# anemo4.net
KiCad netlist of a schematic drawn in EAGLE
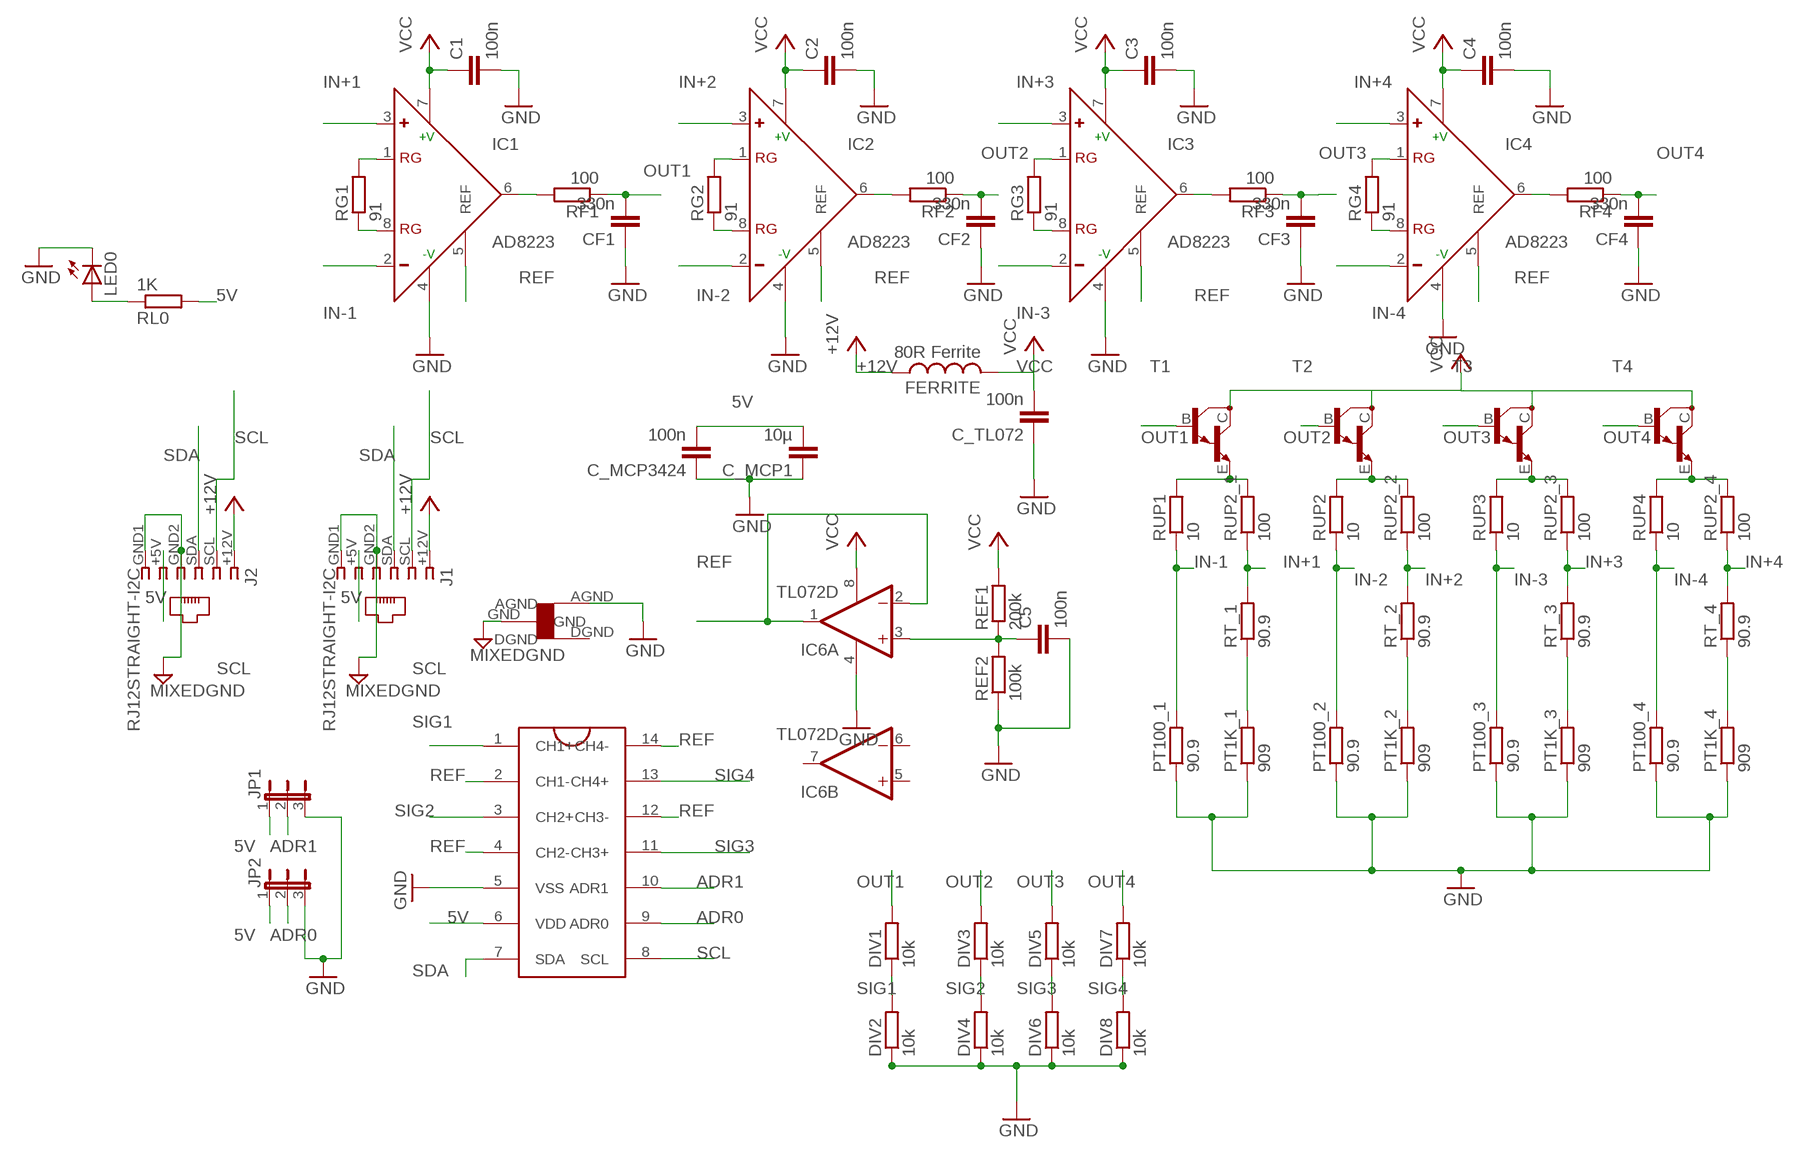
[diagram p0: schematic, sheet 1]

(export (version "E")
  (design (tool "Eeschema 10.0.6"))
  (components
    (comp (ref "C1")
      (value "100n")
      (footprint "eagle-import:C1206")
      (libsource (lib "eagle-import") (part "C-EUC1206"))
    )
    (comp (ref "C2")
      (value "100n")
      (footprint "eagle-import:C1206")
      (libsource (lib "eagle-import") (part "C-EUC1206"))
    )
    (comp (ref "C3")
      (value "100n")
      (footprint "eagle-import:C1206")
      (libsource (lib "eagle-import") (part "C-EUC1206"))
    )
    (comp (ref "C4")
      (value "100n")
      (footprint "eagle-import:C1206")
      (libsource (lib "eagle-import") (part "C-EUC1206"))
    )
    (comp (ref "C5")
      (value "100n")
      (footprint "eagle-import:C1206")
      (libsource (lib "eagle-import") (part "C-EUC1206"))
    )
    (comp (ref "CF1")
      (value "330n")
      (footprint "eagle-import:C1206")
      (libsource (lib "eagle-import") (part "C-EUC1206"))
    )
    (comp (ref "CF2")
      (value "330n")
      (footprint "eagle-import:C1206")
      (libsource (lib "eagle-import") (part "C-EUC1206"))
    )
    (comp (ref "CF3")
      (value "330n")
      (footprint "eagle-import:C1206")
      (libsource (lib "eagle-import") (part "C-EUC1206"))
    )
    (comp (ref "CF4")
      (value "330n")
      (footprint "eagle-import:C1206")
      (libsource (lib "eagle-import") (part "C-EUC1206"))
    )
    (comp (ref "C_MCP1")
      (value "10µ")
      (footprint "eagle-import:C1206")
      (libsource (lib "eagle-import") (part "C-EUC1206"))
    )
    (comp (ref "C_MCP3424")
      (value "100n")
      (footprint "eagle-import:C1206")
      (libsource (lib "eagle-import") (part "C-EUC1206"))
    )
    (comp (ref "C_TL072")
      (value "100n")
      (footprint "eagle-import:C1206")
      (libsource (lib "eagle-import") (part "C-EUC1206"))
    )
    (comp (ref "DIV1")
      (value "10k")
      (footprint "eagle-import:M1206")
      (libsource (lib "eagle-import") (part "R-EU_M1206"))
    )
    (comp (ref "DIV2")
      (value "10k")
      (footprint "eagle-import:M1206")
      (libsource (lib "eagle-import") (part "R-EU_M1206"))
    )
    (comp (ref "DIV3")
      (value "10k")
      (footprint "eagle-import:M1206")
      (libsource (lib "eagle-import") (part "R-EU_M1206"))
    )
    (comp (ref "DIV4")
      (value "10k")
      (footprint "eagle-import:M1206")
      (libsource (lib "eagle-import") (part "R-EU_M1206"))
    )
    (comp (ref "DIV5")
      (value "10k")
      (footprint "eagle-import:M1206")
      (libsource (lib "eagle-import") (part "R-EU_M1206"))
    )
    (comp (ref "DIV6")
      (value "10k")
      (footprint "eagle-import:M1206")
      (libsource (lib "eagle-import") (part "R-EU_M1206"))
    )
    (comp (ref "DIV7")
      (value "10k")
      (footprint "eagle-import:M1206")
      (libsource (lib "eagle-import") (part "R-EU_M1206"))
    )
    (comp (ref "DIV8")
      (value "10k")
      (footprint "eagle-import:M1206")
      (libsource (lib "eagle-import") (part "R-EU_M1206"))
    )
    (comp (ref "FERRITE")
      (value "80R Ferrite")
      (footprint "eagle-import:L3216C")
      (libsource (lib "eagle-import") (part "L-USL3216C"))
    )
    (comp (ref "IC1")
      (value "AD8223")
      (footprint "eagle-import:SO8")
      (fields (field (name "MPN") "AD620AR"))
      (libsource (lib "eagle-import") (part "AD620R"))
    )
    (comp (ref "IC2")
      (value "AD8223")
      (footprint "eagle-import:SO8")
      (fields (field (name "MPN") "AD620AR"))
      (libsource (lib "eagle-import") (part "AD620R"))
    )
    (comp (ref "IC3")
      (value "AD8223")
      (footprint "eagle-import:SO8")
      (fields (field (name "MPN") "AD620AR"))
      (libsource (lib "eagle-import") (part "AD620R"))
    )
    (comp (ref "IC4")
      (value "AD8223")
      (footprint "eagle-import:SO8")
      (fields (field (name "MPN") "AD620AR"))
      (libsource (lib "eagle-import") (part "AD620R"))
    )
    (comp (ref "IC6")
      (value "TL072D")
      (footprint "eagle-import:SO08")
      (libsource (lib "eagle-import") (part "TL072D"))
    )
    (comp (ref "J1")
      (value "RJ12STRAIGHT-I2C")
      (footprint "eagle-import:RJ12-STRAIGHT-I2C")
      (libsource (lib "eagle-import") (part "RJ12STRAIGHT-I2C"))
    )
    (comp (ref "J2")
      (value "RJ12STRAIGHT-I2C")
      (footprint "eagle-import:RJ12-STRAIGHT-I2C")
      (libsource (lib "eagle-import") (part "RJ12STRAIGHT-I2C"))
    )
    (comp (ref "JP1")
      (value "JP2E")
      (footprint "eagle-import:JP2")
      (libsource (lib "eagle-import") (part "JP2E"))
    )
    (comp (ref "JP2")
      (value "JP2E")
      (footprint "eagle-import:JP2")
      (libsource (lib "eagle-import") (part "JP2E"))
    )
    (comp (ref "LED0")
      (value "LED1206")
      (footprint "eagle-import:LED-1206")
      (libsource (lib "eagle-import") (part "LED1206"))
    )
    (comp (ref "PT1K_1")
      (value "909")
      (footprint "eagle-import:M1206")
      (libsource (lib "eagle-import") (part "R-EU_M1206"))
    )
    (comp (ref "PT1K_2")
      (value "909")
      (footprint "eagle-import:M1206")
      (libsource (lib "eagle-import") (part "R-EU_M1206"))
    )
    (comp (ref "PT1K_3")
      (value "909")
      (footprint "eagle-import:M1206")
      (libsource (lib "eagle-import") (part "R-EU_M1206"))
    )
    (comp (ref "PT1K_4")
      (value "909")
      (footprint "eagle-import:M1206")
      (libsource (lib "eagle-import") (part "R-EU_M1206"))
    )
    (comp (ref "PT100_1")
      (value "90.9")
      (footprint "eagle-import:M1206")
      (libsource (lib "eagle-import") (part "R-EU_M1206"))
    )
    (comp (ref "PT100_2")
      (value "90.9")
      (footprint "eagle-import:M1206")
      (libsource (lib "eagle-import") (part "R-EU_M1206"))
    )
    (comp (ref "PT100_3")
      (value "90.9")
      (footprint "eagle-import:M1206")
      (libsource (lib "eagle-import") (part "R-EU_M1206"))
    )
    (comp (ref "PT100_4")
      (value "90.9")
      (footprint "eagle-import:M1206")
      (libsource (lib "eagle-import") (part "R-EU_M1206"))
    )
    (comp (ref "REF1")
      (value "200k")
      (footprint "eagle-import:M1206")
      (libsource (lib "eagle-import") (part "R-EU_M1206"))
    )
    (comp (ref "REF2")
      (value "100k")
      (footprint "eagle-import:M1206")
      (libsource (lib "eagle-import") (part "R-EU_M1206"))
    )
    (comp (ref "RF1")
      (value "100")
      (footprint "eagle-import:M1206")
      (libsource (lib "eagle-import") (part "R-EU_M1206"))
    )
    (comp (ref "RF2")
      (value "100")
      (footprint "eagle-import:M1206")
      (libsource (lib "eagle-import") (part "R-EU_M1206"))
    )
    (comp (ref "RF3")
      (value "100")
      (footprint "eagle-import:M1206")
      (libsource (lib "eagle-import") (part "R-EU_M1206"))
    )
    (comp (ref "RF4")
      (value "100")
      (footprint "eagle-import:M1206")
      (libsource (lib "eagle-import") (part "R-EU_M1206"))
    )
    (comp (ref "RG1")
      (value "91")
      (footprint "eagle-import:M1206")
      (libsource (lib "eagle-import") (part "R-EU_M1206"))
    )
    (comp (ref "RG2")
      (value "91")
      (footprint "eagle-import:M1206")
      (libsource (lib "eagle-import") (part "R-EU_M1206"))
    )
    (comp (ref "RG3")
      (value "91")
      (footprint "eagle-import:M1206")
      (libsource (lib "eagle-import") (part "R-EU_M1206"))
    )
    (comp (ref "RG4")
      (value "91")
      (footprint "eagle-import:M1206")
      (libsource (lib "eagle-import") (part "R-EU_M1206"))
    )
    (comp (ref "RL0")
      (value "1K")
      (footprint "eagle-import:M1206")
      (libsource (lib "eagle-import") (part "R-EU_M1206"))
    )
    (comp (ref "RT_1")
      (value "90.9")
      (footprint "eagle-import:M1206")
      (libsource (lib "eagle-import") (part "R-EU_M1206"))
    )
    (comp (ref "RT_2")
      (value "90.9")
      (footprint "eagle-import:M1206")
      (libsource (lib "eagle-import") (part "R-EU_M1206"))
    )
    (comp (ref "RT_3")
      (value "90.9")
      (footprint "eagle-import:M1206")
      (libsource (lib "eagle-import") (part "R-EU_M1206"))
    )
    (comp (ref "RT_4")
      (value "90.9")
      (footprint "eagle-import:M1206")
      (libsource (lib "eagle-import") (part "R-EU_M1206"))
    )
    (comp (ref "RUP1")
      (value "10")
      (footprint "eagle-import:M1206")
      (libsource (lib "eagle-import") (part "R-EU_M1206"))
    )
    (comp (ref "RUP2")
      (value "10")
      (footprint "eagle-import:M1206")
      (libsource (lib "eagle-import") (part "R-EU_M1206"))
    )
    (comp (ref "RUP2_1")
      (value "100")
      (footprint "eagle-import:M1206")
      (libsource (lib "eagle-import") (part "R-EU_M1206"))
    )
    (comp (ref "RUP2_2")
      (value "100")
      (footprint "eagle-import:M1206")
      (libsource (lib "eagle-import") (part "R-EU_M1206"))
    )
    (comp (ref "RUP2_3")
      (value "100")
      (footprint "eagle-import:M1206")
      (libsource (lib "eagle-import") (part "R-EU_M1206"))
    )
    (comp (ref "RUP2_4")
      (value "100")
      (footprint "eagle-import:M1206")
      (libsource (lib "eagle-import") (part "R-EU_M1206"))
    )
    (comp (ref "RUP3")
      (value "10")
      (footprint "eagle-import:M1206")
      (libsource (lib "eagle-import") (part "R-EU_M1206"))
    )
    (comp (ref "RUP4")
      (value "10")
      (footprint "eagle-import:M1206")
      (libsource (lib "eagle-import") (part "R-EU_M1206"))
    )
    (comp (ref "T1")
      (value "MMBTA13LT1-NPN_DARL-SOT23-BEC")
      (footprint "eagle-import:SOT23-BEC")
      (libsource (lib "eagle-import") (part "-NPN_DARL-SOT23-BECMMBTA13LT1"))
    )
    (comp (ref "T2")
      (value "MMBTA13LT1-NPN_DARL-SOT23-BEC")
      (footprint "eagle-import:SOT23-BEC")
      (libsource (lib "eagle-import") (part "-NPN_DARL-SOT23-BECMMBTA13LT1"))
    )
    (comp (ref "T3")
      (value "MMBTA13LT1-NPN_DARL-SOT23-BEC")
      (footprint "eagle-import:SOT23-BEC")
      (libsource (lib "eagle-import") (part "-NPN_DARL-SOT23-BECMMBTA13LT1"))
    )
    (comp (ref "T4")
      (value "MMBTA13LT1-NPN_DARL-SOT23-BEC")
      (footprint "eagle-import:SOT23-BEC")
      (libsource (lib "eagle-import") (part "-NPN_DARL-SOT23-BECMMBTA13LT1"))
    )
    (comp (ref "U$1")
      (value "MCP3424(SO14)")
      (footprint "eagle-import:14LDSOIC")
      (libsource (lib "eagle-import") (part "MCP3424(SO14)"))
    )
    (comp (ref "U$2")
      (value "STARGND")
      (footprint "eagle-import:STAR")
      (libsource (lib "eagle-import") (part "STARGND"))
    )
  )
  (nets
    (net (code "1") (name "+12V") (class "Default")
      (node (ref "FERRITE") (pin "1") (pinfunction "1_1") (pintype "passive"))
      (node (ref "J1") (pin "+12V") (pinfunction "1_+12V") (pintype "bidirectional"))
      (node (ref "J2") (pin "+12V") (pinfunction "1_+12V") (pintype "bidirectional"))
    )
    (net (code "2") (name "/5V") (class "Default")
      (node (ref "C_MCP1") (pin "2") (pinfunction "2_2") (pintype "passive"))
      (node (ref "C_MCP3424") (pin "2") (pinfunction "2_2") (pintype "passive"))
      (node (ref "J1") (pin "+5V") (pinfunction "5_+5V") (pintype "bidirectional"))
      (node (ref "J2") (pin "+5V") (pinfunction "5_+5V") (pintype "bidirectional"))
      (node (ref "JP1") (pin "1") (pinfunction "1_1") (pintype "passive"))
      (node (ref "JP2") (pin "1") (pinfunction "1_1") (pintype "passive"))
      (node (ref "RL0") (pin "2") (pinfunction "2_2") (pintype "passive"))
      (node (ref "U$1") (pin "6") (pinfunction "VDD_6") (pintype "bidirectional"))
    )
    (net (code "3") (name "/ADR0") (class "Default")
      (node (ref "JP2") (pin "2") (pinfunction "2_2") (pintype "passive"))
      (node (ref "U$1") (pin "9") (pinfunction "ADR0_9") (pintype "bidirectional"))
    )
    (net (code "4") (name "/ADR1") (class "Default")
      (node (ref "JP1") (pin "2") (pinfunction "2_2") (pintype "passive"))
      (node (ref "U$1") (pin "10") (pinfunction "ADR1_10") (pintype "bidirectional"))
    )
    (net (code "5") (name "/IN+1") (class "Default")
      (node (ref "IC1") (pin "3") (pinfunction "+_3") (pintype "input"))
      (node (ref "RT_1") (pin "2") (pinfunction "2_2") (pintype "passive"))
      (node (ref "RUP2_1") (pin "1") (pinfunction "1_1") (pintype "passive"))
    )
    (net (code "6") (name "/IN+2") (class "Default")
      (node (ref "IC2") (pin "3") (pinfunction "+_3") (pintype "input"))
      (node (ref "RT_2") (pin "2") (pinfunction "2_2") (pintype "passive"))
      (node (ref "RUP2_2") (pin "1") (pinfunction "1_1") (pintype "passive"))
    )
    (net (code "7") (name "/IN+3") (class "Default")
      (node (ref "IC3") (pin "3") (pinfunction "+_3") (pintype "input"))
      (node (ref "RT_3") (pin "2") (pinfunction "2_2") (pintype "passive"))
      (node (ref "RUP2_3") (pin "1") (pinfunction "1_1") (pintype "passive"))
    )
    (net (code "8") (name "/IN+4") (class "Default")
      (node (ref "IC4") (pin "3") (pinfunction "+_3") (pintype "input"))
      (node (ref "RT_4") (pin "2") (pinfunction "2_2") (pintype "passive"))
      (node (ref "RUP2_4") (pin "1") (pinfunction "1_1") (pintype "passive"))
    )
    (net (code "9") (name "/IN-1") (class "Default")
      (node (ref "IC1") (pin "2") (pinfunction "-_2") (pintype "input"))
      (node (ref "PT100_1") (pin "2") (pinfunction "2_2") (pintype "passive"))
      (node (ref "RUP1") (pin "1") (pinfunction "1_1") (pintype "passive"))
    )
    (net (code "10") (name "/IN-2") (class "Default")
      (node (ref "IC2") (pin "2") (pinfunction "-_2") (pintype "input"))
      (node (ref "PT100_2") (pin "2") (pinfunction "2_2") (pintype "passive"))
      (node (ref "RUP2") (pin "1") (pinfunction "1_1") (pintype "passive"))
    )
    (net (code "11") (name "/IN-3") (class "Default")
      (node (ref "IC3") (pin "2") (pinfunction "-_2") (pintype "input"))
      (node (ref "PT100_3") (pin "2") (pinfunction "2_2") (pintype "passive"))
      (node (ref "RUP3") (pin "1") (pinfunction "1_1") (pintype "passive"))
    )
    (net (code "12") (name "/IN-4") (class "Default")
      (node (ref "IC4") (pin "2") (pinfunction "-_2") (pintype "input"))
      (node (ref "PT100_4") (pin "2") (pinfunction "2_2") (pintype "passive"))
      (node (ref "RUP4") (pin "1") (pinfunction "1_1") (pintype "passive"))
    )
    (net (code "13") (name "/OUT1") (class "Default")
      (node (ref "CF1") (pin "2") (pinfunction "2_2") (pintype "passive"))
      (node (ref "DIV1") (pin "2") (pinfunction "2_2") (pintype "passive"))
      (node (ref "RF1") (pin "1") (pinfunction "1_1") (pintype "passive"))
      (node (ref "T1") (pin "B") (pinfunction "B_B") (pintype "passive"))
    )
    (net (code "14") (name "/OUT2") (class "Default")
      (node (ref "CF2") (pin "2") (pinfunction "2_2") (pintype "passive"))
      (node (ref "DIV3") (pin "2") (pinfunction "2_2") (pintype "passive"))
      (node (ref "RF2") (pin "1") (pinfunction "1_1") (pintype "passive"))
      (node (ref "T2") (pin "B") (pinfunction "B_B") (pintype "passive"))
    )
    (net (code "15") (name "/OUT3") (class "Default")
      (node (ref "CF3") (pin "2") (pinfunction "2_2") (pintype "passive"))
      (node (ref "DIV5") (pin "2") (pinfunction "2_2") (pintype "passive"))
      (node (ref "RF3") (pin "1") (pinfunction "1_1") (pintype "passive"))
      (node (ref "T3") (pin "B") (pinfunction "B_B") (pintype "passive"))
    )
    (net (code "16") (name "/OUT4") (class "Default")
      (node (ref "CF4") (pin "2") (pinfunction "2_2") (pintype "passive"))
      (node (ref "DIV7") (pin "2") (pinfunction "2_2") (pintype "passive"))
      (node (ref "RF4") (pin "1") (pinfunction "1_1") (pintype "passive"))
      (node (ref "T4") (pin "B") (pinfunction "B_B") (pintype "passive"))
    )
    (net (code "17") (name "/REF") (class "Default")
      (node (ref "IC1") (pin "5") (pinfunction "REF_5") (pintype "passive"))
      (node (ref "IC2") (pin "5") (pinfunction "REF_5") (pintype "passive"))
      (node (ref "IC3") (pin "5") (pinfunction "REF_5") (pintype "passive"))
      (node (ref "IC4") (pin "5") (pinfunction "REF_5") (pintype "passive"))
      (node (ref "IC6") (pin "1") (pinfunction "OUT_1") (pintype "output"))
      (node (ref "IC6") (pin "2") (pinfunction "-IN_2") (pintype "input"))
      (node (ref "U$1") (pin "12") (pinfunction "CH3-_12") (pintype "bidirectional"))
      (node (ref "U$1") (pin "14") (pinfunction "CH4-_14") (pintype "bidirectional"))
      (node (ref "U$1") (pin "2") (pinfunction "CH1-_2") (pintype "bidirectional"))
      (node (ref "U$1") (pin "4") (pinfunction "CH2-_4") (pintype "bidirectional"))
    )
    (net (code "18") (name "/SCL") (class "Default")
      (node (ref "J1") (pin "SCL") (pinfunction "2_SCL") (pintype "bidirectional"))
      (node (ref "J2") (pin "SCL") (pinfunction "2_SCL") (pintype "bidirectional"))
      (node (ref "U$1") (pin "8") (pinfunction "SCL_8") (pintype "bidirectional"))
    )
    (net (code "19") (name "/SDA") (class "Default")
      (node (ref "J1") (pin "SDA") (pinfunction "3_SDA") (pintype "bidirectional"))
      (node (ref "J2") (pin "SDA") (pinfunction "3_SDA") (pintype "bidirectional"))
      (node (ref "U$1") (pin "7") (pinfunction "SDA_7") (pintype "bidirectional"))
    )
    (net (code "20") (name "/SIG1") (class "Default")
      (node (ref "DIV1") (pin "1") (pinfunction "1_1") (pintype "passive"))
      (node (ref "DIV2") (pin "2") (pinfunction "2_2") (pintype "passive"))
      (node (ref "U$1") (pin "1") (pinfunction "CH1+_1") (pintype "bidirectional"))
    )
    (net (code "21") (name "/SIG2") (class "Default")
      (node (ref "DIV3") (pin "1") (pinfunction "1_1") (pintype "passive"))
      (node (ref "DIV4") (pin "2") (pinfunction "2_2") (pintype "passive"))
      (node (ref "U$1") (pin "3") (pinfunction "CH2+_3") (pintype "bidirectional"))
    )
    (net (code "22") (name "/SIG3") (class "Default")
      (node (ref "DIV5") (pin "1") (pinfunction "1_1") (pintype "passive"))
      (node (ref "DIV6") (pin "2") (pinfunction "2_2") (pintype "passive"))
      (node (ref "U$1") (pin "11") (pinfunction "CH3+_11") (pintype "bidirectional"))
    )
    (net (code "23") (name "/SIG4") (class "Default")
      (node (ref "DIV7") (pin "1") (pinfunction "1_1") (pintype "passive"))
      (node (ref "DIV8") (pin "2") (pinfunction "2_2") (pintype "passive"))
      (node (ref "U$1") (pin "13") (pinfunction "CH4+_13") (pintype "bidirectional"))
    )
    (net (code "24") (name "GND") (class "Default")
      (node (ref "C1") (pin "2") (pinfunction "2_2") (pintype "passive"))
      (node (ref "C2") (pin "2") (pinfunction "2_2") (pintype "passive"))
      (node (ref "C3") (pin "2") (pinfunction "2_2") (pintype "passive"))
      (node (ref "C4") (pin "2") (pinfunction "2_2") (pintype "passive"))
      (node (ref "C5") (pin "2") (pinfunction "2_2") (pintype "passive"))
      (node (ref "CF1") (pin "1") (pinfunction "1_1") (pintype "passive"))
      (node (ref "CF2") (pin "1") (pinfunction "1_1") (pintype "passive"))
      (node (ref "CF3") (pin "1") (pinfunction "1_1") (pintype "passive"))
      (node (ref "CF4") (pin "1") (pinfunction "1_1") (pintype "passive"))
      (node (ref "C_MCP1") (pin "1") (pinfunction "1_1") (pintype "passive"))
      (node (ref "C_MCP3424") (pin "1") (pinfunction "1_1") (pintype "passive"))
      (node (ref "C_TL072") (pin "1") (pinfunction "1_1") (pintype "passive"))
      (node (ref "DIV2") (pin "1") (pinfunction "1_1") (pintype "passive"))
      (node (ref "DIV4") (pin "1") (pinfunction "1_1") (pintype "passive"))
      (node (ref "DIV6") (pin "1") (pinfunction "1_1") (pintype "passive"))
      (node (ref "DIV8") (pin "1") (pinfunction "1_1") (pintype "passive"))
      (node (ref "IC1") (pin "4") (pinfunction "-V_4") (pintype "power_in"))
      (node (ref "IC2") (pin "4") (pinfunction "-V_4") (pintype "power_in"))
      (node (ref "IC3") (pin "4") (pinfunction "-V_4") (pintype "power_in"))
      (node (ref "IC4") (pin "4") (pinfunction "-V_4") (pintype "power_in"))
      (node (ref "IC6") (pin "4") (pinfunction "V-_4") (pintype "power_in"))
      (node (ref "JP1") (pin "3") (pinfunction "3_3") (pintype "passive"))
      (node (ref "JP2") (pin "3") (pinfunction "3_3") (pintype "passive"))
      (node (ref "LED0") (pin "C") (pinfunction "C_C") (pintype "passive"))
      (node (ref "PT100_1") (pin "1") (pinfunction "1_1") (pintype "passive"))
      (node (ref "PT100_2") (pin "1") (pinfunction "1_1") (pintype "passive"))
      (node (ref "PT100_3") (pin "1") (pinfunction "1_1") (pintype "passive"))
      (node (ref "PT100_4") (pin "1") (pinfunction "1_1") (pintype "passive"))
      (node (ref "PT1K_1") (pin "1") (pinfunction "1_1") (pintype "passive"))
      (node (ref "PT1K_2") (pin "1") (pinfunction "1_1") (pintype "passive"))
      (node (ref "PT1K_3") (pin "1") (pinfunction "1_1") (pintype "passive"))
      (node (ref "PT1K_4") (pin "1") (pinfunction "1_1") (pintype "passive"))
      (node (ref "REF2") (pin "1") (pinfunction "1_1") (pintype "passive"))
      (node (ref "U$1") (pin "5") (pinfunction "VSS_5") (pintype "bidirectional"))
      (node (ref "U$2") (pin "AGND") (pinfunction "AGND_AGND") (pintype "output"))
    )
    (net (code "25") (name "MIXEDGND") (class "Default")
      (node (ref "J1") (pin "GND1") (pinfunction "6_GND1") (pintype "bidirectional"))
      (node (ref "J1") (pin "GND2") (pinfunction "4_GND2") (pintype "bidirectional"))
      (node (ref "J2") (pin "GND1") (pinfunction "6_GND1") (pintype "bidirectional"))
      (node (ref "J2") (pin "GND2") (pinfunction "4_GND2") (pintype "bidirectional"))
      (node (ref "U$2") (pin "GND") (pinfunction "GND_GND") (pintype "power_in"))
    )
    (net (code "26") (name "Net-(IC1-OUT)") (class "Default")
      (node (ref "IC1") (pin "6") (pinfunction "OUT_6") (pintype "output"))
      (node (ref "RF1") (pin "2") (pinfunction "2_2") (pintype "passive"))
    )
    (net (code "27") (name "Net-(IC1-RG-Pad1)") (class "Default")
      (node (ref "IC1") (pin "1") (pinfunction "RG_1") (pintype "passive"))
      (node (ref "RG1") (pin "2") (pinfunction "2_2") (pintype "passive"))
    )
    (net (code "28") (name "Net-(IC1-RG-Pad8)") (class "Default")
      (node (ref "IC1") (pin "8") (pinfunction "RG_8") (pintype "passive"))
      (node (ref "RG1") (pin "1") (pinfunction "1_1") (pintype "passive"))
    )
    (net (code "29") (name "Net-(IC2-OUT)") (class "Default")
      (node (ref "IC2") (pin "6") (pinfunction "OUT_6") (pintype "output"))
      (node (ref "RF2") (pin "2") (pinfunction "2_2") (pintype "passive"))
    )
    (net (code "30") (name "Net-(IC2-RG-Pad1)") (class "Default")
      (node (ref "IC2") (pin "1") (pinfunction "RG_1") (pintype "passive"))
      (node (ref "RG2") (pin "2") (pinfunction "2_2") (pintype "passive"))
    )
    (net (code "31") (name "Net-(IC2-RG-Pad8)") (class "Default")
      (node (ref "IC2") (pin "8") (pinfunction "RG_8") (pintype "passive"))
      (node (ref "RG2") (pin "1") (pinfunction "1_1") (pintype "passive"))
    )
    (net (code "32") (name "Net-(IC3-OUT)") (class "Default")
      (node (ref "IC3") (pin "6") (pinfunction "OUT_6") (pintype "output"))
      (node (ref "RF3") (pin "2") (pinfunction "2_2") (pintype "passive"))
    )
    (net (code "33") (name "Net-(IC3-RG-Pad1)") (class "Default")
      (node (ref "IC3") (pin "1") (pinfunction "RG_1") (pintype "passive"))
      (node (ref "RG3") (pin "2") (pinfunction "2_2") (pintype "passive"))
    )
    (net (code "34") (name "Net-(IC3-RG-Pad8)") (class "Default")
      (node (ref "IC3") (pin "8") (pinfunction "RG_8") (pintype "passive"))
      (node (ref "RG3") (pin "1") (pinfunction "1_1") (pintype "passive"))
    )
    (net (code "35") (name "Net-(IC4-OUT)") (class "Default")
      (node (ref "IC4") (pin "6") (pinfunction "OUT_6") (pintype "output"))
      (node (ref "RF4") (pin "2") (pinfunction "2_2") (pintype "passive"))
    )
    (net (code "36") (name "Net-(IC4-RG-Pad1)") (class "Default")
      (node (ref "IC4") (pin "1") (pinfunction "RG_1") (pintype "passive"))
      (node (ref "RG4") (pin "2") (pinfunction "2_2") (pintype "passive"))
    )
    (net (code "37") (name "Net-(IC4-RG-Pad8)") (class "Default")
      (node (ref "IC4") (pin "8") (pinfunction "RG_8") (pintype "passive"))
      (node (ref "RG4") (pin "1") (pinfunction "1_1") (pintype "passive"))
    )
    (net (code "38") (name "Net-(IC6A-+IN)") (class "Default")
      (node (ref "C5") (pin "1") (pinfunction "1_1") (pintype "passive"))
      (node (ref "IC6") (pin "3") (pinfunction "+IN_3") (pintype "input"))
      (node (ref "REF1") (pin "1") (pinfunction "1_1") (pintype "passive"))
      (node (ref "REF2") (pin "2") (pinfunction "2_2") (pintype "passive"))
    )
    (net (code "39") (name "Net-(LED0-PadA)") (class "Default")
      (node (ref "LED0") (pin "A") (pinfunction "A_A") (pintype "passive"))
      (node (ref "RL0") (pin "1") (pinfunction "1_1") (pintype "passive"))
    )
    (net (code "40") (name "Net-(PT1K_1-Pad2)") (class "Default")
      (node (ref "PT1K_1") (pin "2") (pinfunction "2_2") (pintype "passive"))
      (node (ref "RT_1") (pin "1") (pinfunction "1_1") (pintype "passive"))
    )
    (net (code "41") (name "Net-(PT1K_2-Pad2)") (class "Default")
      (node (ref "PT1K_2") (pin "2") (pinfunction "2_2") (pintype "passive"))
      (node (ref "RT_2") (pin "1") (pinfunction "1_1") (pintype "passive"))
    )
    (net (code "42") (name "Net-(PT1K_3-Pad2)") (class "Default")
      (node (ref "PT1K_3") (pin "2") (pinfunction "2_2") (pintype "passive"))
      (node (ref "RT_3") (pin "1") (pinfunction "1_1") (pintype "passive"))
    )
    (net (code "43") (name "Net-(PT1K_4-Pad2)") (class "Default")
      (node (ref "PT1K_4") (pin "2") (pinfunction "2_2") (pintype "passive"))
      (node (ref "RT_4") (pin "1") (pinfunction "1_1") (pintype "passive"))
    )
    (net (code "44") (name "Net-(RUP1-Pad2)") (class "Default")
      (node (ref "RUP1") (pin "2") (pinfunction "2_2") (pintype "passive"))
      (node (ref "RUP2_1") (pin "2") (pinfunction "2_2") (pintype "passive"))
      (node (ref "T1") (pin "E") (pinfunction "E_E") (pintype "passive"))
    )
    (net (code "45") (name "Net-(RUP2-Pad2)") (class "Default")
      (node (ref "RUP2") (pin "2") (pinfunction "2_2") (pintype "passive"))
      (node (ref "RUP2_2") (pin "2") (pinfunction "2_2") (pintype "passive"))
      (node (ref "T2") (pin "E") (pinfunction "E_E") (pintype "passive"))
    )
    (net (code "46") (name "Net-(RUP2_3-Pad2)") (class "Default")
      (node (ref "RUP2_3") (pin "2") (pinfunction "2_2") (pintype "passive"))
      (node (ref "RUP3") (pin "2") (pinfunction "2_2") (pintype "passive"))
      (node (ref "T3") (pin "E") (pinfunction "E_E") (pintype "passive"))
    )
    (net (code "47") (name "Net-(RUP2_4-Pad2)") (class "Default")
      (node (ref "RUP2_4") (pin "2") (pinfunction "2_2") (pintype "passive"))
      (node (ref "RUP4") (pin "2") (pinfunction "2_2") (pintype "passive"))
      (node (ref "T4") (pin "E") (pinfunction "E_E") (pintype "passive"))
    )
    (net (code "48") (name "VCC") (class "Default")
      (node (ref "C1") (pin "1") (pinfunction "1_1") (pintype "passive"))
      (node (ref "C2") (pin "1") (pinfunction "1_1") (pintype "passive"))
      (node (ref "C3") (pin "1") (pinfunction "1_1") (pintype "passive"))
      (node (ref "C4") (pin "1") (pinfunction "1_1") (pintype "passive"))
      (node (ref "C_TL072") (pin "2") (pinfunction "2_2") (pintype "passive"))
      (node (ref "FERRITE") (pin "2") (pinfunction "2_2") (pintype "passive"))
      (node (ref "IC1") (pin "7") (pinfunction "+V_7") (pintype "power_in"))
      (node (ref "IC2") (pin "7") (pinfunction "+V_7") (pintype "power_in"))
      (node (ref "IC3") (pin "7") (pinfunction "+V_7") (pintype "power_in"))
      (node (ref "IC4") (pin "7") (pinfunction "+V_7") (pintype "power_in"))
      (node (ref "IC6") (pin "8") (pinfunction "V+_8") (pintype "power_in"))
      (node (ref "REF1") (pin "2") (pinfunction "2_2") (pintype "passive"))
      (node (ref "T1") (pin "C") (pinfunction "C_C") (pintype "passive"))
      (node (ref "T2") (pin "C") (pinfunction "C_C") (pintype "passive"))
      (node (ref "T3") (pin "C") (pinfunction "C_C") (pintype "passive"))
      (node (ref "T4") (pin "C") (pinfunction "C_C") (pintype "passive"))
    )
    (net (code "49") (name "unconnected-(IC6B-+IN-Pad5)") (class "Default")
      (node (ref "IC6") (pin "5") (pinfunction "+IN_5") (pintype "input"))
    )
    (net (code "50") (name "unconnected-(IC6B--IN-Pad6)") (class "Default")
      (node (ref "IC6") (pin "6") (pinfunction "-IN_6") (pintype "input"))
    )
    (net (code "51") (name "unconnected-(IC6B-OUT-Pad7)") (class "Default")
      (node (ref "IC6") (pin "7") (pinfunction "OUT_7") (pintype "output"))
    )
    (net (code "52") (name "unconnected-(U$2-PadDGND)") (class "Default")
      (node (ref "U$2") (pin "DGND") (pinfunction "DGND_DGND") (pintype "output"))
    )
  )
)
